# JS7628_base_power_v1_0.net
KiCad netlist of a schematic drawn in Altium Designer
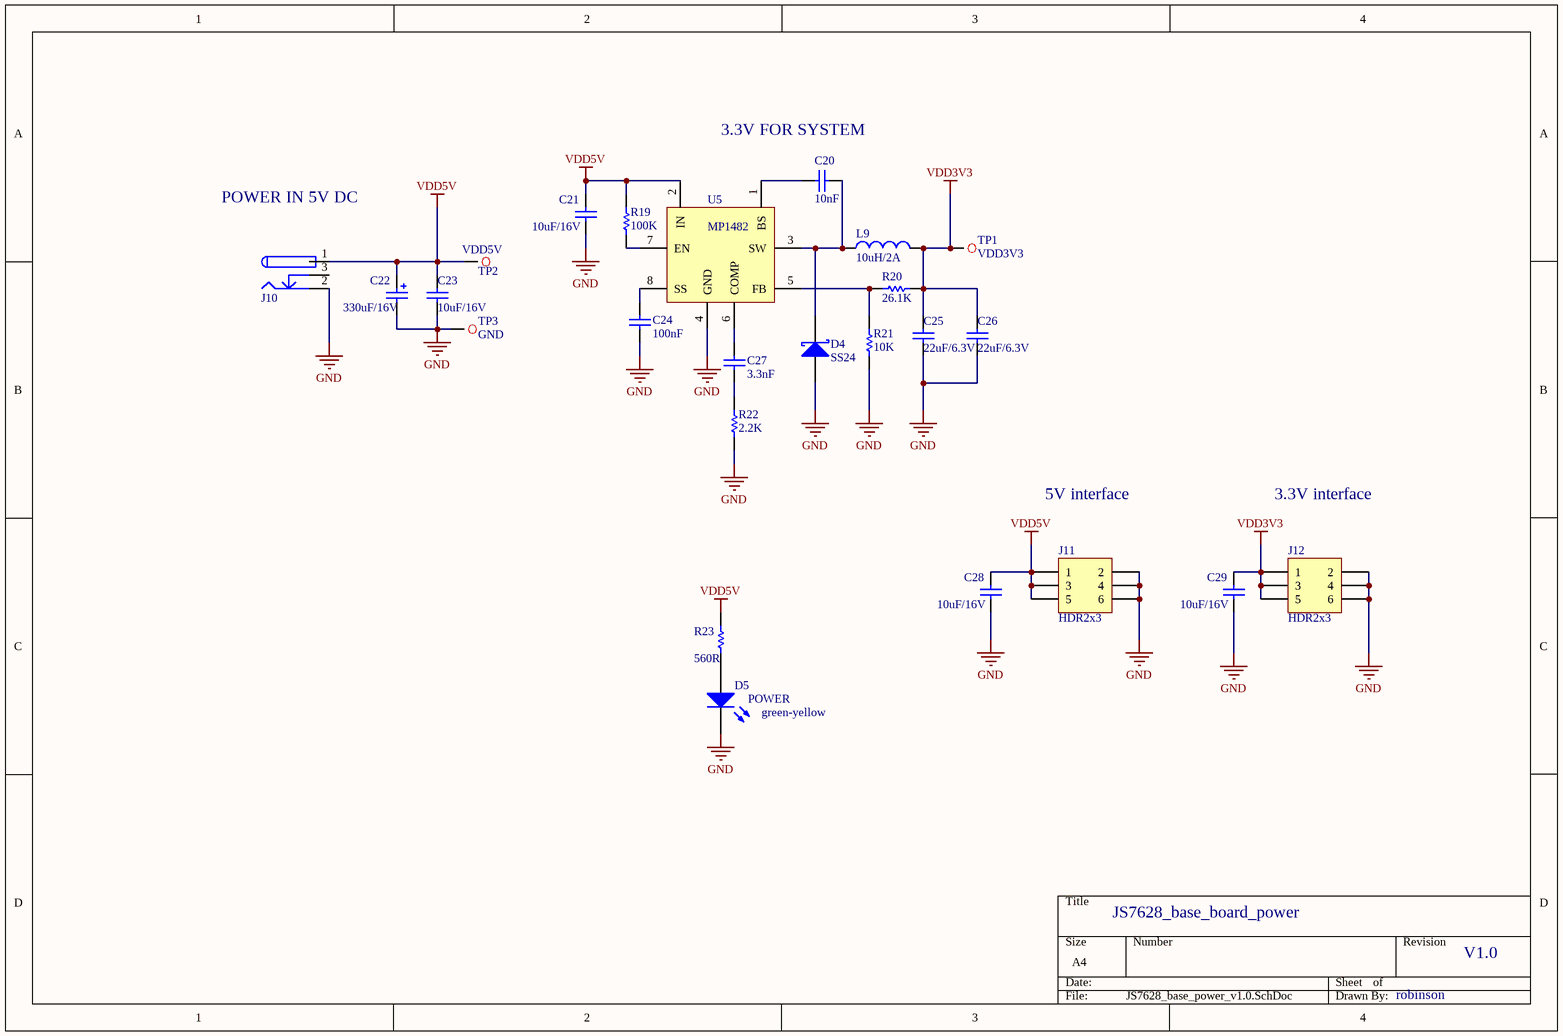
[diagram p0: JS7628_base_power_v1.0.SchDoc]

(export (version "E")
  (design (tool "Eeschema 10.0.6"))
  (components
    (comp (ref "C20")
      (value "10nF")
      (footprint "0603")
      (fields (field (name "Comment") "CAP-SMT"))
      (libsource (lib "MyMiscellaneousDevice") (part "CAP-SMT"))
    )
    (comp (ref "C21")
      (value "10uF/16V")
      (footprint "0603")
      (fields (field (name "Comment") "CAP-SMT"))
      (libsource (lib "MyMiscellaneousDevice") (part "CAP-SMT"))
    )
    (comp (ref "C22")
      (value "330uF/16V")
      (footprint "RB2.5-6.5")
      (fields (field (name "Comment") "cap-pol"))
      (libsource (lib "MyMiscellaneousDevice") (part "cap-pol"))
    )
    (comp (ref "C23")
      (value "10uF/16V")
      (footprint "0603")
      (fields (field (name "Comment") "CAP-SMT"))
      (libsource (lib "MyMiscellaneousDevice") (part "CAP-SMT"))
    )
    (comp (ref "C24")
      (value "100nF")
      (footprint "0603")
      (fields (field (name "Comment") "CAP-SMT"))
      (libsource (lib "MyMiscellaneousDevice") (part "CAP-SMT"))
    )
    (comp (ref "C25")
      (value "22uF/6.3V")
      (footprint "0603")
      (fields (field (name "Comment") "CAP-SMT"))
      (libsource (lib "MyMiscellaneousDevice") (part "CAP-SMT"))
    )
    (comp (ref "C26")
      (value "22uF/6.3V")
      (footprint "0603")
      (fields (field (name "Comment") "CAP-SMT"))
      (libsource (lib "MyMiscellaneousDevice") (part "CAP-SMT"))
    )
    (comp (ref "C27")
      (value "3.3nF")
      (footprint "0603")
      (fields (field (name "Comment") "CAP-SMT"))
      (libsource (lib "MyMiscellaneousDevice") (part "CAP-SMT"))
    )
    (comp (ref "C28")
      (value "10uF/16V")
      (footprint "0603")
      (fields (field (name "Comment") "CAP-SMT"))
      (libsource (lib "MyMiscellaneousDevice") (part "CAP-SMT"))
    )
    (comp (ref "C29")
      (value "10uF/16V")
      (footprint "0603")
      (fields (field (name "Comment") "CAP-SMT"))
      (libsource (lib "MyMiscellaneousDevice") (part "CAP-SMT"))
    )
    (comp (ref "D4") (value "SS24") (footprint "SMB") (libsource (lib "MyMiscellaneousDevice") (part "SS24")))
    (comp (ref "D5")
      (value "POWER")
      (footprint "0805-LED")
      (fields (field (name "ALTIUM_VALUE") "green-yellow"))
      (libsource (lib "MyMiscellaneousDevice") (part "LED"))
    )
    (comp (ref "J10")
      (value "DC-005")
      (footprint "DC-005")
      (libsource (lib "MyMiscellaneousConnector") (part "DC-005"))
    )
    (comp (ref "J11")
      (value "HDR2x3")
      (footprint "HDR2x3-2.54mm")
      (libsource (lib "MyMiscellaneousConnector") (part "HDR2x3"))
    )
    (comp (ref "J12")
      (value "HDR2x3")
      (footprint "HDR2x3-2.54mm")
      (libsource (lib "MyMiscellaneousConnector") (part "HDR2x3"))
    )
    (comp (ref "L9")
      (value "10uH/2A")
      (footprint "CDRH-7x7")
      (fields (field (name "Comment") "inductor"))
      (libsource (lib "MyMiscellaneousDevice") (part "inductor"))
    )
    (comp (ref "R19")
      (value "100K")
      (footprint "0603")
      (fields (field (name "Comment") "RES-SMT"))
      (libsource (lib "MyMiscellaneousDevice") (part "RES-SMT"))
    )
    (comp (ref "R20")
      (value "26.1K")
      (footprint "0603")
      (fields (field (name "Comment") "RES-SMT"))
      (libsource (lib "MyMiscellaneousDevice") (part "RES-SMT"))
    )
    (comp (ref "R21")
      (value "10K")
      (footprint "0603")
      (fields (field (name "Comment") "RES-SMT"))
      (libsource (lib "MyMiscellaneousDevice") (part "RES-SMT"))
    )
    (comp (ref "R22")
      (value "2.2K")
      (footprint "0603")
      (fields (field (name "Comment") "RES-SMT"))
      (libsource (lib "MyMiscellaneousDevice") (part "RES-SMT"))
    )
    (comp (ref "R23")
      (value "560R")
      (footprint "0603")
      (fields (field (name "Comment") "RES-SMT"))
      (libsource (lib "MyMiscellaneousDevice") (part "RES-SMT"))
    )
    (comp (ref "TP1")
      (value "VDD3V3")
      (footprint "Test Point")
      (libsource (lib "MyMiscellaneousConnector") (part "Test Point"))
    )
    (comp (ref "TP2")
      (value "VDD5V")
      (footprint "Test Point")
      (libsource (lib "MyMiscellaneousConnector") (part "Test Point"))
    )
    (comp (ref "TP3")
      (value "GND")
      (footprint "Test Point")
      (libsource (lib "MyMiscellaneousConnector") (part "Test Point"))
    )
    (comp (ref "U5")
      (value "MP1482")
      (footprint "SOIC-8P")
      (libsource (lib "MyMiscellaneousDevice") (part "MP1482"))
    )
  )
  (nets
    (net (code "1") (name "GND") (class "Default")
      (node (ref "C21") (pin "1") (pinfunction "1_1") (pintype "passive"))
      (node (ref "C22") (pin "2") (pinfunction "2_2") (pintype "passive"))
      (node (ref "C23") (pin "1") (pinfunction "1_1") (pintype "passive"))
      (node (ref "C24") (pin "1") (pinfunction "1_1") (pintype "passive"))
      (node (ref "C25") (pin "1") (pinfunction "1_1") (pintype "passive"))
      (node (ref "C26") (pin "1") (pinfunction "1_1") (pintype "passive"))
      (node (ref "C28") (pin "1") (pinfunction "1_1") (pintype "passive"))
      (node (ref "C29") (pin "1") (pinfunction "1_1") (pintype "passive"))
      (node (ref "D4") (pin "1") (pinfunction "A_1") (pintype "passive"))
      (node (ref "D5") (pin "2") (pinfunction "K_2") (pintype "passive"))
      (node (ref "J10") (pin "2") (pinfunction "2_2") (pintype "passive"))
      (node (ref "J11") (pin "2") (pinfunction "2_2") (pintype "passive"))
      (node (ref "J11") (pin "4") (pinfunction "4_4") (pintype "passive"))
      (node (ref "J11") (pin "6") (pinfunction "6_6") (pintype "passive"))
      (node (ref "J12") (pin "2") (pinfunction "2_2") (pintype "passive"))
      (node (ref "J12") (pin "4") (pinfunction "4_4") (pintype "passive"))
      (node (ref "J12") (pin "6") (pinfunction "6_6") (pintype "passive"))
      (node (ref "R21") (pin "2") (pinfunction "2_2") (pintype "passive"))
      (node (ref "R22") (pin "1") (pinfunction "1_1") (pintype "passive"))
      (node (ref "TP3") (pin "1") (pinfunction "1_1") (pintype "passive"))
      (node (ref "U5") (pin "4") (pinfunction "GND_4") (pintype "passive"))
    )
    (net (code "2") (name "Net-(C27-Pad1)") (class "Default")
      (node (ref "C27") (pin "1") (pinfunction "1_1") (pintype "passive"))
      (node (ref "R22") (pin "2") (pinfunction "2_2") (pintype "passive"))
    )
    (net (code "3") (name "Net-(D4-K)") (class "Default")
      (node (ref "C20") (pin "2") (pinfunction "2_2") (pintype "passive"))
      (node (ref "D4") (pin "2") (pinfunction "K_2") (pintype "passive"))
      (node (ref "L9") (pin "1") (pinfunction "1_1") (pintype "passive"))
      (node (ref "U5") (pin "3") (pinfunction "SW_3") (pintype "passive"))
    )
    (net (code "4") (name "Net-(D5-A)") (class "Default")
      (node (ref "D5") (pin "1") (pinfunction "A_1") (pintype "passive"))
      (node (ref "R23") (pin "1") (pinfunction "1_1") (pintype "passive"))
    )
    (net (code "5") (name "Net-(U5-BS)") (class "Default")
      (node (ref "C20") (pin "1") (pinfunction "1_1") (pintype "passive"))
      (node (ref "U5") (pin "1") (pinfunction "BS_1") (pintype "passive"))
    )
    (net (code "6") (name "Net-(U5-COMP)") (class "Default")
      (node (ref "C27") (pin "2") (pinfunction "2_2") (pintype "passive"))
      (node (ref "U5") (pin "6") (pinfunction "COMP_6") (pintype "passive"))
    )
    (net (code "7") (name "Net-(U5-EN)") (class "Default")
      (node (ref "R19") (pin "2") (pinfunction "2_2") (pintype "passive"))
      (node (ref "U5") (pin "7") (pinfunction "EN_7") (pintype "passive"))
    )
    (net (code "8") (name "Net-(U5-FB)") (class "Default")
      (node (ref "R20") (pin "2") (pinfunction "2_2") (pintype "passive"))
      (node (ref "R21") (pin "1") (pinfunction "1_1") (pintype "passive"))
      (node (ref "U5") (pin "5") (pinfunction "FB_5") (pintype "passive"))
    )
    (net (code "9") (name "Net-(U5-SS)") (class "Default")
      (node (ref "C24") (pin "2") (pinfunction "2_2") (pintype "passive"))
      (node (ref "U5") (pin "8") (pinfunction "SS_8") (pintype "passive"))
    )
    (net (code "10") (name "VDD3V3") (class "Default")
      (node (ref "C25") (pin "2") (pinfunction "2_2") (pintype "passive"))
      (node (ref "C26") (pin "2") (pinfunction "2_2") (pintype "passive"))
      (node (ref "C29") (pin "2") (pinfunction "2_2") (pintype "passive"))
      (node (ref "J12") (pin "1") (pinfunction "1_1") (pintype "passive"))
      (node (ref "J12") (pin "3") (pinfunction "3_3") (pintype "passive"))
      (node (ref "J12") (pin "5") (pinfunction "5_5") (pintype "passive"))
      (node (ref "L9") (pin "2") (pinfunction "2_2") (pintype "passive"))
      (node (ref "R20") (pin "1") (pinfunction "1_1") (pintype "passive"))
      (node (ref "TP1") (pin "1") (pinfunction "1_1") (pintype "passive"))
    )
    (net (code "11") (name "VDD5V") (class "Default")
      (node (ref "C21") (pin "2") (pinfunction "2_2") (pintype "passive"))
      (node (ref "C22") (pin "1") (pinfunction "1_1") (pintype "passive"))
      (node (ref "C23") (pin "2") (pinfunction "2_2") (pintype "passive"))
      (node (ref "C28") (pin "2") (pinfunction "2_2") (pintype "passive"))
      (node (ref "J10") (pin "1") (pinfunction "1_1") (pintype "passive"))
      (node (ref "J11") (pin "1") (pinfunction "1_1") (pintype "passive"))
      (node (ref "J11") (pin "3") (pinfunction "3_3") (pintype "passive"))
      (node (ref "J11") (pin "5") (pinfunction "5_5") (pintype "passive"))
      (node (ref "R19") (pin "1") (pinfunction "1_1") (pintype "passive"))
      (node (ref "R23") (pin "2") (pinfunction "2_2") (pintype "passive"))
      (node (ref "TP2") (pin "1") (pinfunction "1_1") (pintype "passive"))
      (node (ref "U5") (pin "2") (pinfunction "IN_2") (pintype "passive"))
    )
    (net (code "12") (name "unconnected-(J10-Pad3)") (class "Default")
      (node (ref "J10") (pin "3") (pinfunction "3_3") (pintype "passive"))
    )
  )
)
